# Bi_Dir_Circuit.net
KiCad netlist of a schematic drawn in Altium Designer
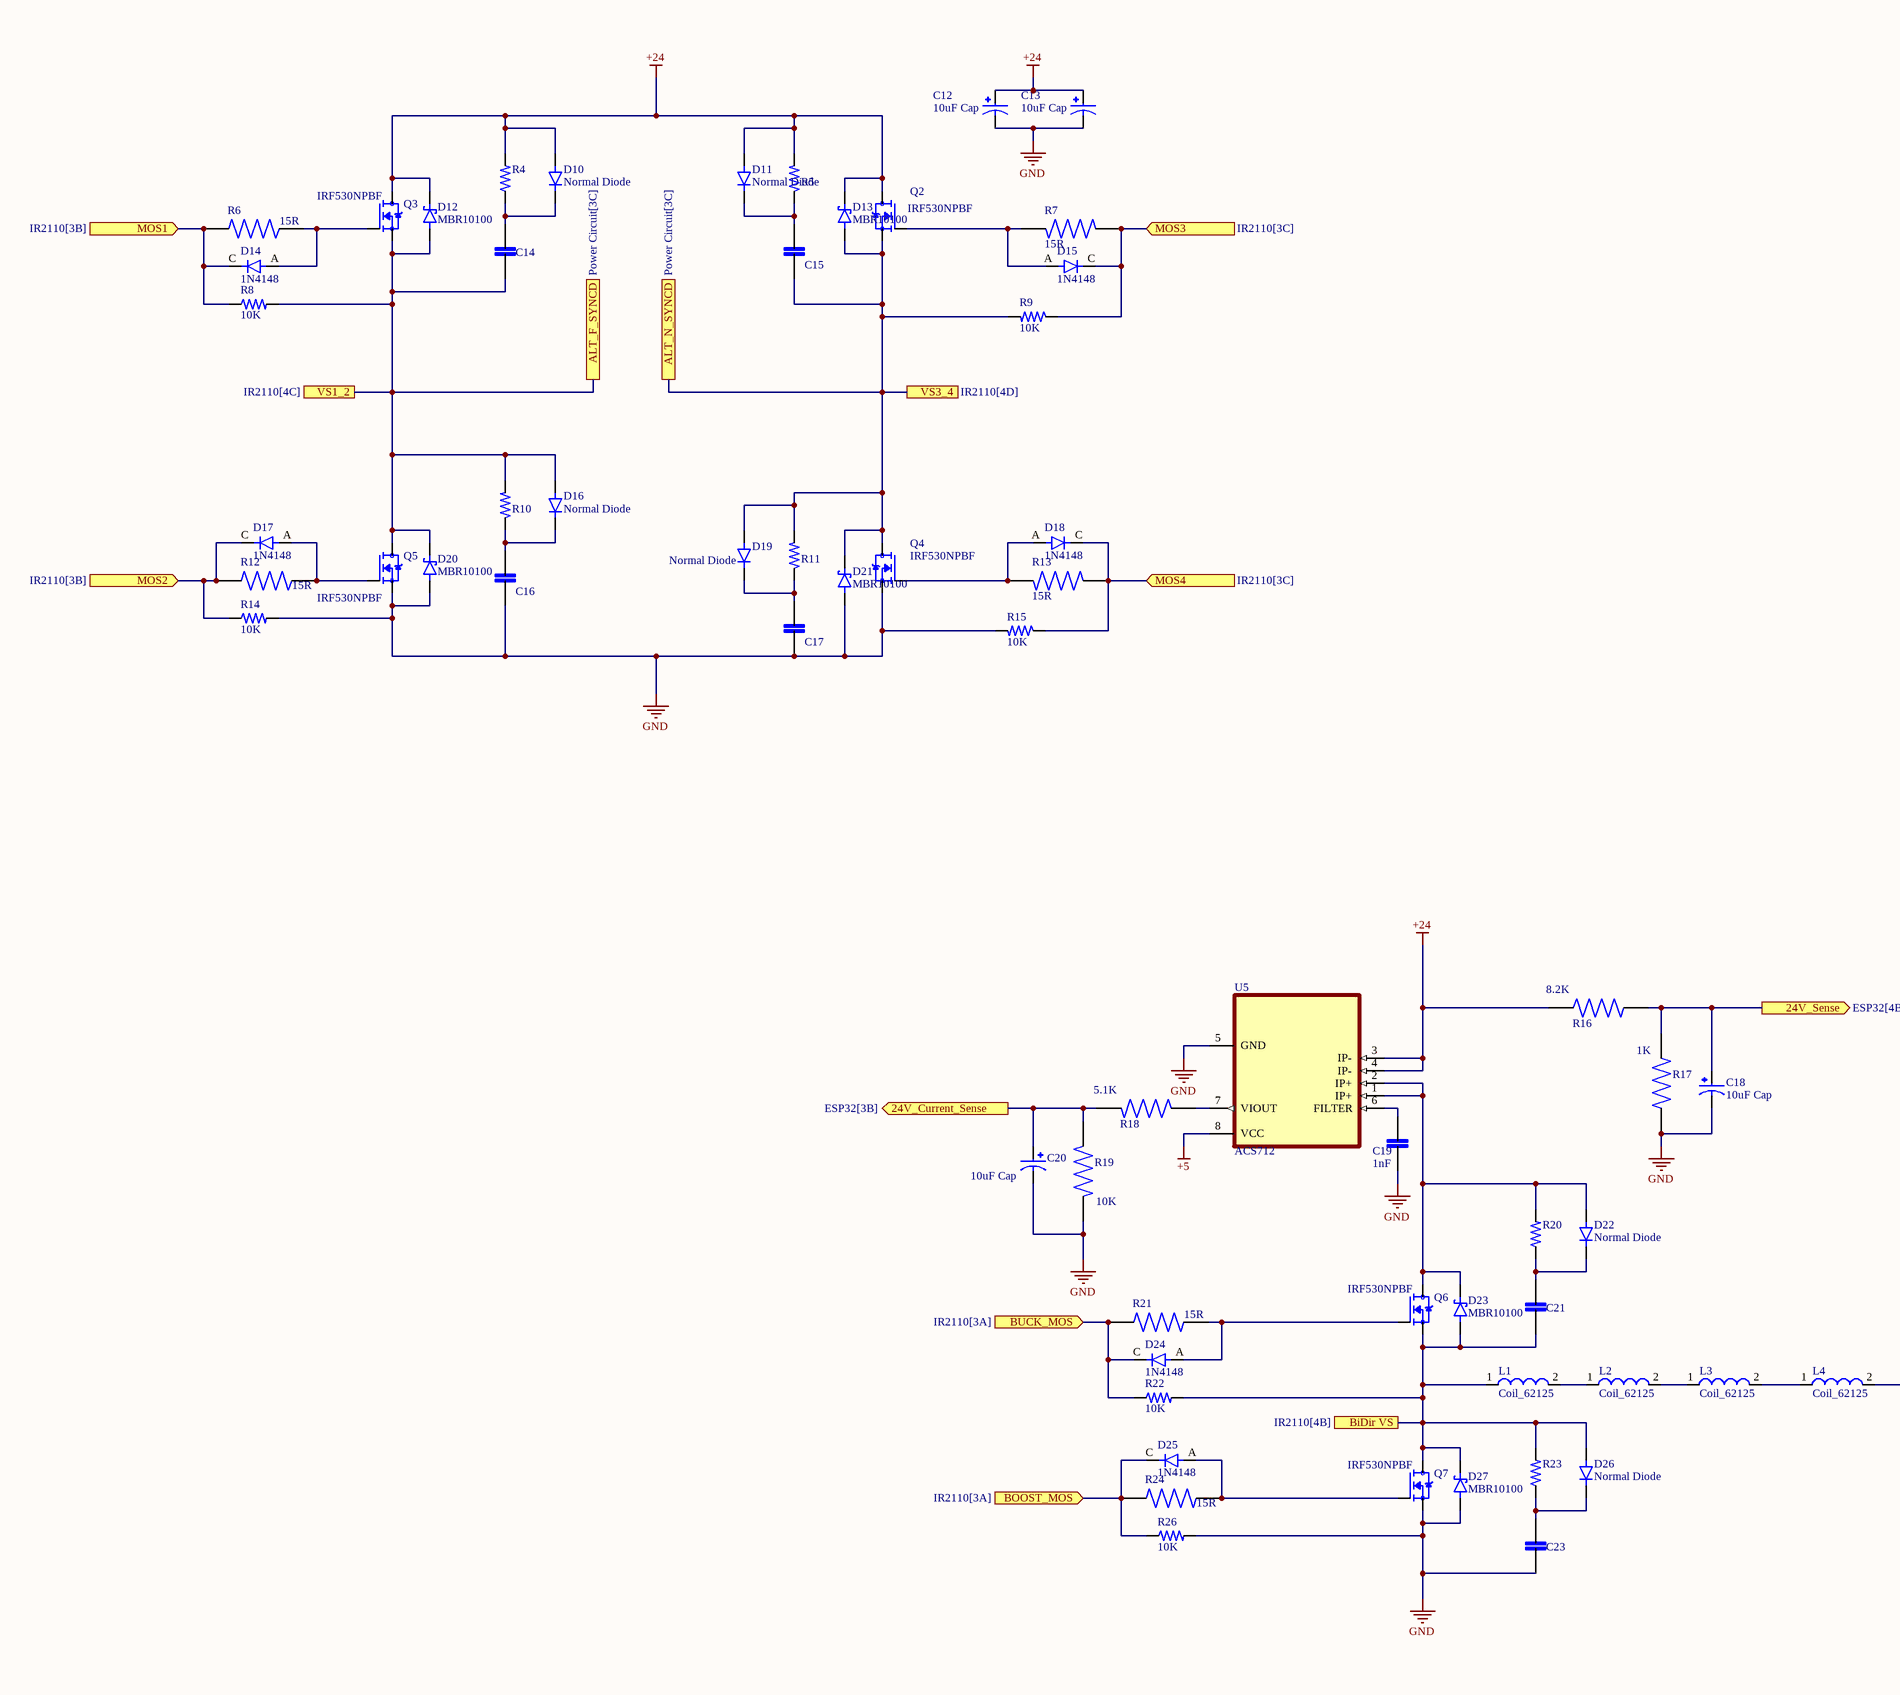
[diagram p0: Bi_Dir_Circuit.SchDoc, left]
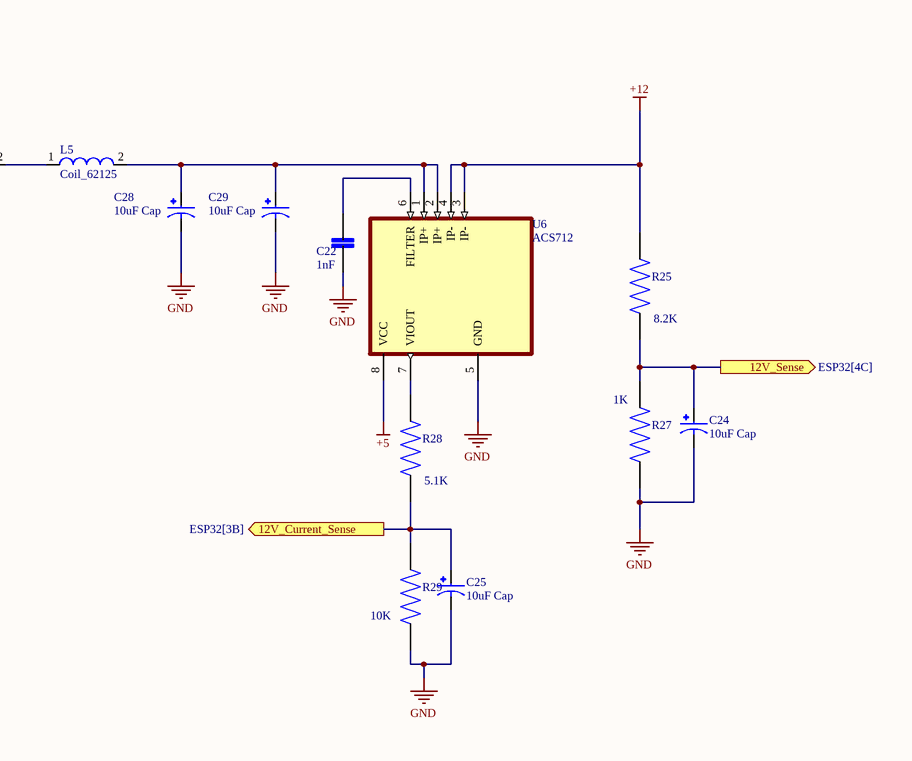
[diagram p1: Bi_Dir_Circuit.SchDoc, right]

(export (version "E")
  (design (tool "Eeschema 10.0.6"))
  (components
    (comp (ref "C12")
      (value "10uF Cap")
      (footprint "2200uF_Cap")
      (description "CAP ALUM 10UF 20% 50V RADIAL")
      (fields (field (name "MP") "ECE-A1HN100UI") (field (name "MF") "Panasonic"))
      (libsource (lib "MySCH_Library") (part "10uF Cap"))
    )
    (comp (ref "C13")
      (value "10uF Cap")
      (footprint "2200uF_Cap")
      (description "CAP ALUM 10UF 20% 50V RADIAL")
      (fields (field (name "MP") "ECE-A1HN100UI") (field (name "MF") "Panasonic"))
      (libsource (lib "MySCH_Library") (part "10uF Cap"))
    )
    (comp (ref "C14")
      (value "Ceramic Capacitor")
      (footprint "Ceramic Capacitor")
      (fields (field (name "MP") "LD051A121KAB2A") (field (name "MF") "AVX"))
      (libsource (lib "Capacitors Through Hole") (part "Ceramic Capacitor"))
    )
    (comp (ref "C15")
      (value "Ceramic Capacitor")
      (footprint "Ceramic Capacitor")
      (fields (field (name "MP") "LD051A121KAB2A") (field (name "MF") "AVX"))
      (libsource (lib "") (part "Ceramic Capacitor_1"))
    )
    (comp (ref "C16")
      (value "Ceramic Capacitor")
      (footprint "Ceramic Capacitor")
      (fields (field (name "MP") "LD051A121KAB2A") (field (name "MF") "AVX"))
      (libsource (lib "") (part "Ceramic Capacitor_1"))
    )
    (comp (ref "C17")
      (value "Ceramic Capacitor")
      (footprint "Ceramic Capacitor")
      (fields (field (name "MP") "LD051A121KAB2A") (field (name "MF") "AVX"))
      (libsource (lib "") (part "Ceramic Capacitor_1"))
    )
    (comp (ref "C18")
      (value "10uF Cap")
      (footprint "CAP_10uF")
      (description "CAP ALUM 10UF 20% 50V RADIAL")
      (fields (field (name "MP") "ECE-A1HN100UI") (field (name "MF") "Panasonic"))
      (libsource (lib "MySCH_Library") (part "10uF Cap"))
    )
    (comp (ref "C19")
      (value "1nF")
      (footprint "Ceramic Capacitor")
      (fields (field (name "MP") "LD051A121KAB2A") (field (name "MF") "AVX"))
      (libsource (lib "Capacitors Through Hole") (part "Ceramic Capacitor"))
    )
    (comp (ref "C20")
      (value "10uF Cap")
      (footprint "CAP_10uF")
      (description "CAP ALUM 10UF 20% 50V RADIAL")
      (fields (field (name "MP") "ECE-A1HN100UI") (field (name "MF") "Panasonic"))
      (libsource (lib "") (part "10uF Cap_1"))
    )
    (comp (ref "C21")
      (value "Ceramic Capacitor")
      (footprint "Ceramic Capacitor")
      (fields (field (name "MP") "LD051A121KAB2A") (field (name "MF") "AVX"))
      (libsource (lib "Capacitors Through Hole") (part "Ceramic Capacitor"))
    )
    (comp (ref "C22")
      (value "1nF")
      (footprint "Ceramic Capacitor")
      (fields (field (name "MP") "LD051A121KAB2A") (field (name "MF") "AVX"))
      (libsource (lib "Capacitors Through Hole") (part "Ceramic Capacitor"))
    )
    (comp (ref "C23")
      (value "Ceramic Capacitor")
      (footprint "Ceramic Capacitor")
      (fields (field (name "MP") "LD051A121KAB2A") (field (name "MF") "AVX"))
      (libsource (lib "Capacitors Through Hole") (part "Ceramic Capacitor"))
    )
    (comp (ref "C24")
      (value "10uF Cap")
      (footprint "CAP_10uF")
      (description "CAP ALUM 10UF 20% 50V RADIAL")
      (fields (field (name "MP") "ECE-A1HN100UI") (field (name "MF") "Panasonic"))
      (libsource (lib "MySCH_Library") (part "10uF Cap"))
    )
    (comp (ref "C25")
      (value "10uF Cap")
      (footprint "CAP_10uF")
      (description "CAP ALUM 10UF 20% 50V RADIAL")
      (fields (field (name "MP") "ECE-A1HN100UI") (field (name "MF") "Panasonic"))
      (libsource (lib "MySCH_Library") (part "10uF Cap"))
    )
    (comp (ref "C28")
      (value "10uF Cap")
      (footprint "2200uF_Cap")
      (description "CAP ALUM 10UF 20% 50V RADIAL")
      (fields (field (name "MP") "ECE-A1HN100UI") (field (name "MF") "Panasonic"))
      (libsource (lib "MySCH_Library") (part "10uF Cap"))
    )
    (comp (ref "C29")
      (value "10uF Cap")
      (footprint "2200uF_Cap")
      (description "CAP ALUM 10UF 20% 50V RADIAL")
      (fields (field (name "MP") "ECE-A1HN100UI") (field (name "MF") "Panasonic"))
      (libsource (lib "MySCH_Library") (part "10uF Cap"))
    )
    (comp (ref "D10")
      (value "Normal Diode")
      (footprint "Common Trhough Hole")
      (fields (field (name "MF") "NTE Electronics, Inc.") (field (name "MP") "1N4007"))
      (libsource (lib "Diodes Through Hole") (part "Normal Diode"))
    )
    (comp (ref "D11")
      (value "Normal Diode")
      (footprint "Common Trhough Hole")
      (fields (field (name "MF") "NTE Electronics, Inc.") (field (name "MP") "1N4007"))
      (libsource (lib "Diodes Through Hole") (part "Normal Diode"))
    )
    (comp (ref "D12")
      (value "MBR10100")
      (footprint "MBR10100")
      (fields (field (name "MF") "Diodes Inc.") (field (name "MP") "1N5817-T"))
      (libsource (lib "Diodes Through Hole") (part "MBR10100"))
    )
    (comp (ref "D13")
      (value "MBR10100")
      (footprint "MBR10100")
      (fields (field (name "MF") "Diodes Inc.") (field (name "MP") "1N5817-T"))
      (libsource (lib "Diodes Through Hole") (part "MBR10100"))
    )
    (comp (ref "D14")
      (value "1N4148")
      (footprint "1N4007 DIODE")
      (description "Diode Standard 1000 V 1A Through Hole DO-41")
      (fields (field (name "MF") "NTE Electronics, Inc.") (field (name "MP") "1N4007"))
      (libsource (lib "MySCH_Library") (part "1N4007"))
    )
    (comp (ref "D15")
      (value "1N4148")
      (footprint "1N4007 DIODE")
      (description "Diode Standard 1000 V 1A Through Hole DO-41")
      (fields (field (name "MF") "NTE Electronics, Inc.") (field (name "MP") "1N4007"))
      (libsource (lib "MySCH_Library") (part "1N4007"))
    )
    (comp (ref "D16")
      (value "Normal Diode")
      (footprint "Common Trhough Hole")
      (fields (field (name "MF") "NTE Electronics, Inc.") (field (name "MP") "1N4007"))
      (libsource (lib "Diodes Through Hole") (part "Normal Diode"))
    )
    (comp (ref "D17")
      (value "1N4148")
      (footprint "1N4007 DIODE")
      (description "Diode Standard 1000 V 1A Through Hole DO-41")
      (fields (field (name "MF") "NTE Electronics, Inc.") (field (name "MP") "1N4007"))
      (libsource (lib "MySCH_Library") (part "1N4007"))
    )
    (comp (ref "D18")
      (value "1N4148")
      (footprint "1N4007 DIODE")
      (description "Diode Standard 1000 V 1A Through Hole DO-41")
      (fields (field (name "MF") "NTE Electronics, Inc.") (field (name "MP") "1N4007"))
      (libsource (lib "MySCH_Library") (part "1N4007"))
    )
    (comp (ref "D19")
      (value "Normal Diode")
      (footprint "Common Trhough Hole")
      (fields (field (name "MF") "NTE Electronics, Inc.") (field (name "MP") "1N4007"))
      (libsource (lib "Diodes Through Hole") (part "Normal Diode"))
    )
    (comp (ref "D20")
      (value "MBR10100")
      (footprint "MBR10100")
      (fields (field (name "MF") "Diodes Inc.") (field (name "MP") "1N5817-T"))
      (libsource (lib "Diodes Through Hole") (part "MBR10100"))
    )
    (comp (ref "D21")
      (value "MBR10100")
      (footprint "MBR10100")
      (fields (field (name "MF") "Diodes Inc.") (field (name "MP") "1N5817-T"))
      (libsource (lib "Diodes Through Hole") (part "MBR10100"))
    )
    (comp (ref "D22")
      (value "Normal Diode")
      (footprint "Common Trhough Hole")
      (fields (field (name "MF") "NTE Electronics, Inc.") (field (name "MP") "1N4007"))
      (libsource (lib "Diodes Through Hole") (part "Normal Diode"))
    )
    (comp (ref "D23")
      (value "MBR10100")
      (footprint "MBR10100")
      (fields (field (name "MF") "Diodes Inc.") (field (name "MP") "1N5817-T"))
      (libsource (lib "Diodes Through Hole") (part "MBR10100"))
    )
    (comp (ref "D24")
      (value "1N4148")
      (footprint "1N4007 DIODE")
      (description "Diode Standard 1000 V 1A Through Hole DO-41")
      (fields (field (name "MF") "NTE Electronics, Inc.") (field (name "MP") "1N4007"))
      (libsource (lib "MySCH_Library") (part "1N4007"))
    )
    (comp (ref "D25")
      (value "1N4148")
      (footprint "1N4007 DIODE")
      (description "Diode Standard 1000 V 1A Through Hole DO-41")
      (fields (field (name "MF") "NTE Electronics, Inc.") (field (name "MP") "1N4007"))
      (libsource (lib "MySCH_Library") (part "1N4007"))
    )
    (comp (ref "D26")
      (value "Normal Diode")
      (footprint "Common Trhough Hole")
      (fields (field (name "MF") "NTE Electronics, Inc.") (field (name "MP") "1N4007"))
      (libsource (lib "Diodes Through Hole") (part "Normal Diode"))
    )
    (comp (ref "D27")
      (value "MBR10100")
      (footprint "MBR10100")
      (fields (field (name "MF") "Diodes Inc.") (field (name "MP") "1N5817-T"))
      (libsource (lib "Diodes Through Hole") (part "MBR10100"))
    )
    (comp (ref "L1")
      (value "Coil_62125")
      (footprint "Coil 65125")
      (description "Inductor Power Wirewound 470uH 10% 1KHz 25Q-Factor Ferrite 210mA 3.3Ohm DCR T/R")
      (fields (field (name "DIGI-KEY_PART_NUMBER") "SDR0604-471KLCT-ND") (field (name "MF") "Bourns"))
      (libsource (lib "MySCH_Library") (part "Coil_62125"))
    )
    (comp (ref "L2")
      (value "Coil_62125")
      (footprint "Coil 65125")
      (description "Inductor Power Wirewound 470uH 10% 1KHz 25Q-Factor Ferrite 210mA 3.3Ohm DCR T/R")
      (fields (field (name "DIGI-KEY_PART_NUMBER") "SDR0604-471KLCT-ND") (field (name "MF") "Bourns"))
      (libsource (lib "MySCH_Library") (part "Coil_62125"))
    )
    (comp (ref "L3")
      (value "Coil_62125")
      (footprint "Coil 65125")
      (description "Inductor Power Wirewound 470uH 10% 1KHz 25Q-Factor Ferrite 210mA 3.3Ohm DCR T/R")
      (fields (field (name "DIGI-KEY_PART_NUMBER") "SDR0604-471KLCT-ND") (field (name "MF") "Bourns"))
      (libsource (lib "MySCH_Library") (part "Coil_62125"))
    )
    (comp (ref "L4")
      (value "Coil_62125")
      (footprint "Coil 65125")
      (description "Inductor Power Wirewound 470uH 10% 1KHz 25Q-Factor Ferrite 210mA 3.3Ohm DCR T/R")
      (fields (field (name "DIGI-KEY_PART_NUMBER") "SDR0604-471KLCT-ND") (field (name "MF") "Bourns"))
      (libsource (lib "MySCH_Library") (part "Coil_62125"))
    )
    (comp (ref "L5")
      (value "Coil_62125")
      (footprint "Coil 65125")
      (description "Inductor Power Wirewound 470uH 10% 1KHz 25Q-Factor Ferrite 210mA 3.3Ohm DCR T/R")
      (fields (field (name "DIGI-KEY_PART_NUMBER") "SDR0604-471KLCT-ND") (field (name "MF") "Bourns"))
      (libsource (lib "MySCH_Library") (part "Coil_62125"))
    )
    (comp (ref "Q2")
      (value "IRF530NPBF")
      (footprint "IRF530N")
      (fields (field (name "MF") "Infineon Technologies"))
      (libsource (lib "MySCH_Library") (part "IRF530NPBF"))
    )
    (comp (ref "Q3")
      (value "IRF530NPBF")
      (footprint "IRF530N")
      (fields (field (name "MF") "Infineon Technologies"))
      (libsource (lib "MySCH_Library") (part "IRF530NPBF"))
    )
    (comp (ref "Q4")
      (value "IRF530NPBF")
      (footprint "IRF530N")
      (fields (field (name "MF") "Infineon Technologies"))
      (libsource (lib "MySCH_Library") (part "IRF530NPBF"))
    )
    (comp (ref "Q5")
      (value "IRF530NPBF")
      (footprint "IRF530N")
      (fields (field (name "MF") "Infineon Technologies"))
      (libsource (lib "MySCH_Library") (part "IRF530NPBF"))
    )
    (comp (ref "Q6")
      (value "IRF530NPBF")
      (footprint "IRF530N")
      (fields (field (name "MF") "Infineon Technologies"))
      (libsource (lib "MySCH_Library") (part "IRF530NPBF"))
    )
    (comp (ref "Q7")
      (value "IRF530NPBF")
      (footprint "IRF530N")
      (fields (field (name "MF") "Infineon Technologies"))
      (libsource (lib "MySCH_Library") (part "IRF530NPBF"))
    )
    (comp (ref "R4")
      (value "Resistor")
      (footprint "Resistor_Through Hole")
      (fields
        (field (name "MP") "2-2176053-0")
        (field (name "TOLERANCE") "1%")
        (field (name "MF") "TE Connectivity")
      )
      (libsource (lib "Resistors Through Hole") (part "Resistor"))
    )
    (comp (ref "R5")
      (value "Resistor")
      (footprint "Resistor_Through Hole")
      (fields
        (field (name "MP") "2-2176053-0")
        (field (name "TOLERANCE") "1%")
        (field (name "MF") "TE Connectivity")
      )
      (libsource (lib "Resistors Through Hole") (part "Resistor"))
    )
    (comp (ref "R6")
      (value "15R")
      (footprint "Resistor_Through Hole")
      (description "1.02 Ohms Â±1% 0.25W, 1/4W Through Hole Resistor Axial Metal Film")
      (fields (field (name "MP") "MFR-25FTE52-1R") (field (name "MF") "Yageo"))
      (libsource (lib "MySCH_Library") (part "Resistor_Through Hole"))
    )
    (comp (ref "R7")
      (value "15R")
      (footprint "Resistor_Through Hole")
      (description "1.02 Ohms Â±1% 0.25W, 1/4W Through Hole Resistor Axial Metal Film")
      (fields (field (name "MP") "MFR-25FTE52-1R") (field (name "MF") "Yageo"))
      (libsource (lib "MySCH_Library") (part "Resistor_Through Hole"))
    )
    (comp (ref "R8")
      (value "10K")
      (footprint "Resistor_Through Hole")
      (fields
        (field (name "MP") "2-2176053-0")
        (field (name "TOLERANCE") "1%")
        (field (name "MF") "TE Connectivity")
      )
      (libsource (lib "Resistors Through Hole") (part "Resistor"))
    )
    (comp (ref "R9")
      (value "10K")
      (footprint "Resistor_Through Hole")
      (fields
        (field (name "MP") "2-2176053-0")
        (field (name "TOLERANCE") "1%")
        (field (name "MF") "TE Connectivity")
      )
      (libsource (lib "Resistors Through Hole") (part "Resistor"))
    )
    (comp (ref "R10")
      (value "Resistor")
      (footprint "Resistor_Through Hole")
      (fields
        (field (name "MP") "2-2176053-0")
        (field (name "TOLERANCE") "1%")
        (field (name "MF") "TE Connectivity")
      )
      (libsource (lib "Resistors Through Hole") (part "Resistor"))
    )
    (comp (ref "R11")
      (value "Resistor")
      (footprint "Resistor_Through Hole")
      (fields
        (field (name "MP") "2-2176053-0")
        (field (name "TOLERANCE") "1%")
        (field (name "MF") "TE Connectivity")
      )
      (libsource (lib "Resistors Through Hole") (part "Resistor"))
    )
    (comp (ref "R12")
      (value "15R")
      (footprint "Resistor_Through Hole")
      (description "1.02 Ohms Â±1% 0.25W, 1/4W Through Hole Resistor Axial Metal Film")
      (fields (field (name "MP") "MFR-25FTE52-1R") (field (name "MF") "Yageo"))
      (libsource (lib "MySCH_Library") (part "Resistor_Through Hole"))
    )
    (comp (ref "R13")
      (value "15R")
      (footprint "Resistor_Through Hole")
      (description "1.02 Ohms Â±1% 0.25W, 1/4W Through Hole Resistor Axial Metal Film")
      (fields (field (name "MP") "MFR-25FTE52-1R") (field (name "MF") "Yageo"))
      (libsource (lib "MySCH_Library") (part "Resistor_Through Hole"))
    )
    (comp (ref "R14")
      (value "10K")
      (footprint "Resistor_Through Hole")
      (fields
        (field (name "MP") "2-2176053-0")
        (field (name "TOLERANCE") "1%")
        (field (name "MF") "TE Connectivity")
      )
      (libsource (lib "Resistors Through Hole") (part "Resistor"))
    )
    (comp (ref "R15")
      (value "10K")
      (footprint "Resistor_Through Hole")
      (fields
        (field (name "MP") "2-2176053-0")
        (field (name "TOLERANCE") "1%")
        (field (name "MF") "TE Connectivity")
      )
      (libsource (lib "Resistors Through Hole") (part "Resistor"))
    )
    (comp (ref "R16")
      (value "8.2K")
      (footprint "Resistor_Through Hole")
      (description "1.02 Ohms Â±1% 0.25W, 1/4W Through Hole Resistor Axial Metal Film")
      (fields (field (name "MP") "MFR-25FTE52-1R") (field (name "MF") "Yageo"))
      (libsource (lib "MySCH_Library") (part "Resistor_Through Hole"))
    )
    (comp (ref "R17")
      (value "1K")
      (footprint "Resistor_Through Hole")
      (description "1.02 Ohms Â±1% 0.25W, 1/4W Through Hole Resistor Axial Metal Film")
      (fields (field (name "MP") "MFR-25FTE52-1R") (field (name "MF") "Yageo"))
      (libsource (lib "MySCH_Library") (part "Resistor_Through Hole"))
    )
    (comp (ref "R18")
      (value "5.1K")
      (footprint "Resistor_Through Hole")
      (description "1.02 Ohms Â±1% 0.25W, 1/4W Through Hole Resistor Axial Metal Film")
      (fields (field (name "MP") "MFR-25FTE52-1R") (field (name "MF") "Yageo"))
      (libsource (lib "MySCH_Library") (part "Resistor_Through Hole"))
    )
    (comp (ref "R19")
      (value "10K")
      (footprint "Resistor_Through Hole")
      (description "1.02 Ohms Â±1% 0.25W, 1/4W Through Hole Resistor Axial Metal Film")
      (fields (field (name "MP") "MFR-25FTE52-1R") (field (name "MF") "Yageo"))
      (libsource (lib "MySCH_Library") (part "Resistor_Through Hole"))
    )
    (comp (ref "R20")
      (value "Resistor")
      (footprint "Resistor_Through Hole")
      (fields
        (field (name "MP") "2-2176053-0")
        (field (name "TOLERANCE") "1%")
        (field (name "MF") "TE Connectivity")
      )
      (libsource (lib "Resistors Through Hole") (part "Resistor"))
    )
    (comp (ref "R21")
      (value "15R")
      (footprint "Resistor_Through Hole")
      (description "1.02 Ohms Â±1% 0.25W, 1/4W Through Hole Resistor Axial Metal Film")
      (fields (field (name "MP") "MFR-25FTE52-1R") (field (name "MF") "Yageo"))
      (libsource (lib "MySCH_Library") (part "Resistor_Through Hole"))
    )
    (comp (ref "R22")
      (value "10K")
      (footprint "Resistor_Through Hole")
      (fields
        (field (name "MP") "2-2176053-0")
        (field (name "TOLERANCE") "1%")
        (field (name "MF") "TE Connectivity")
      )
      (libsource (lib "Resistors Through Hole") (part "Resistor"))
    )
    (comp (ref "R23")
      (value "Resistor")
      (footprint "Resistor_Through Hole")
      (fields
        (field (name "MP") "2-2176053-0")
        (field (name "TOLERANCE") "1%")
        (field (name "MF") "TE Connectivity")
      )
      (libsource (lib "Resistors Through Hole") (part "Resistor"))
    )
    (comp (ref "R24")
      (value "15R")
      (footprint "Resistor_Through Hole")
      (description "1.02 Ohms Â±1% 0.25W, 1/4W Through Hole Resistor Axial Metal Film")
      (fields (field (name "MP") "MFR-25FTE52-1R") (field (name "MF") "Yageo"))
      (libsource (lib "MySCH_Library") (part "Resistor_Through Hole"))
    )
    (comp (ref "R25")
      (value "8.2K")
      (footprint "Resistor_Through Hole")
      (description "1.02 Ohms Â±1% 0.25W, 1/4W Through Hole Resistor Axial Metal Film")
      (fields (field (name "MP") "MFR-25FTE52-1R") (field (name "MF") "Yageo"))
      (libsource (lib "MySCH_Library") (part "Resistor_Through Hole"))
    )
    (comp (ref "R26")
      (value "10K")
      (footprint "Resistor_Through Hole")
      (fields
        (field (name "MP") "2-2176053-0")
        (field (name "TOLERANCE") "1%")
        (field (name "MF") "TE Connectivity")
      )
      (libsource (lib "Resistors Through Hole") (part "Resistor"))
    )
    (comp (ref "R27")
      (value "1K")
      (footprint "Resistor_Through Hole")
      (description "1.02 Ohms Â±1% 0.25W, 1/4W Through Hole Resistor Axial Metal Film")
      (fields (field (name "MP") "MFR-25FTE52-1R") (field (name "MF") "Yageo"))
      (libsource (lib "MySCH_Library") (part "Resistor_Through Hole"))
    )
    (comp (ref "R28")
      (value "5.1K")
      (footprint "Resistor_Through Hole")
      (description "1.02 Ohms Â±1% 0.25W, 1/4W Through Hole Resistor Axial Metal Film")
      (fields (field (name "MP") "MFR-25FTE52-1R") (field (name "MF") "Yageo"))
      (libsource (lib "MySCH_Library") (part "Resistor_Through Hole"))
    )
    (comp (ref "R29")
      (value "10K")
      (footprint "Resistor_Through Hole")
      (description "1.02 Ohms Â±1% 0.25W, 1/4W Through Hole Resistor Axial Metal Film")
      (fields (field (name "MP") "MFR-25FTE52-1R") (field (name "MF") "Yageo"))
      (libsource (lib "MySCH_Library") (part "Resistor_Through Hole"))
    )
    (comp (ref "U5")
      (value "ACS712")
      (footprint "ACS712")
      (description "Current Sensor 5A 1 Channel Hall Effect, Open Loop Bidirectional 8-SOIC (0.154, 3.90mm Width)")
      (fields (field (name "MP") "ACS712ELCTR-05B-T") (field (name "MF") "Allegro MicroSystems LLC"))
      (libsource (lib "Hall Current Sensor") (part "ACS712"))
    )
    (comp (ref "U6")
      (value "ACS712")
      (footprint "ACS712")
      (description "Current Sensor 5A 1 Channel Hall Effect, Open Loop Bidirectional 8-SOIC (0.154, 3.90mm Width)")
      (fields (field (name "MP") "ACS712ELCTR-05B-T") (field (name "MF") "Allegro MicroSystems LLC"))
      (libsource (lib "Hall Current Sensor") (part "ACS712"))
    )
  )
  (nets
    (net (code "1") (name "+5") (class "Default")
      (node (ref "U5") (pin "8") (pinfunction "VCC_8") (pintype "power_in"))
      (node (ref "U6") (pin "8") (pinfunction "VCC_8") (pintype "power_in"))
    )
    (net (code "2") (name "+12") (class "Default")
      (node (ref "R25") (pin "2") (pinfunction "2_2") (pintype "passive"))
      (node (ref "U6") (pin "3") (pinfunction "IP-_3") (pintype "input"))
      (node (ref "U6") (pin "4") (pinfunction "IP-_4") (pintype "input"))
    )
    (net (code "3") (name "+24") (class "Default")
      (node (ref "C12") (pin "P") (pinfunction "P_P") (pintype "passive"))
      (node (ref "C13") (pin "P") (pinfunction "P_P") (pintype "passive"))
      (node (ref "D10") (pin "2") (pinfunction "A_2") (pintype "passive"))
      (node (ref "D11") (pin "2") (pinfunction "A_2") (pintype "passive"))
      (node (ref "D12") (pin "1") (pinfunction "K_1") (pintype "passive"))
      (node (ref "D13") (pin "1") (pinfunction "K_1") (pintype "passive"))
      (node (ref "Q2") (pin "2") (pinfunction "D_2") (pintype "passive"))
      (node (ref "Q3") (pin "2") (pinfunction "D_2") (pintype "passive"))
      (node (ref "R16") (pin "1") (pinfunction "1_1") (pintype "passive"))
      (node (ref "R4") (pin "2") (pinfunction "2_2") (pintype "passive"))
      (node (ref "R5") (pin "2") (pinfunction "2_2") (pintype "passive"))
      (node (ref "U5") (pin "3") (pinfunction "IP-_3") (pintype "input"))
      (node (ref "U5") (pin "4") (pinfunction "IP-_4") (pintype "input"))
    )
    (net (code "4") (name "/12V_Current_Sense") (class "Default")
      (node (ref "C25") (pin "P") (pinfunction "P_P") (pintype "passive"))
      (node (ref "R28") (pin "1") (pinfunction "1_1") (pintype "passive"))
      (node (ref "R29") (pin "2") (pinfunction "2_2") (pintype "passive"))
    )
    (net (code "5") (name "/12V_Sense") (class "Default")
      (node (ref "C24") (pin "P") (pinfunction "P_P") (pintype "passive"))
      (node (ref "R25") (pin "1") (pinfunction "1_1") (pintype "passive"))
      (node (ref "R27") (pin "2") (pinfunction "2_2") (pintype "passive"))
    )
    (net (code "6") (name "/24V_Current_Sense") (class "Default")
      (node (ref "C20") (pin "P") (pinfunction "P_P") (pintype "passive"))
      (node (ref "R18") (pin "1") (pinfunction "1_1") (pintype "passive"))
      (node (ref "R19") (pin "2") (pinfunction "2_2") (pintype "passive"))
    )
    (net (code "7") (name "/24V_Sense") (class "Default")
      (node (ref "C18") (pin "P") (pinfunction "P_P") (pintype "passive"))
      (node (ref "R16") (pin "2") (pinfunction "2_2") (pintype "passive"))
      (node (ref "R17") (pin "2") (pinfunction "2_2") (pintype "passive"))
    )
    (net (code "8") (name "/ALT_F_SYNCD") (class "Default")
      (node (ref "C14") (pin "1") (pinfunction "1_1") (pintype "passive"))
      (node (ref "D12") (pin "3") (pinfunction "A_3") (pintype "passive"))
      (node (ref "D16") (pin "2") (pinfunction "A_2") (pintype "passive"))
      (node (ref "D20") (pin "1") (pinfunction "K_1") (pintype "passive"))
      (node (ref "Q3") (pin "3") (pinfunction "S_3") (pintype "passive"))
      (node (ref "Q5") (pin "2") (pinfunction "D_2") (pintype "passive"))
      (node (ref "R10") (pin "2") (pinfunction "2_2") (pintype "passive"))
      (node (ref "R8") (pin "2") (pinfunction "2_2") (pintype "passive"))
    )
    (net (code "9") (name "/ALT_N_SYNCD") (class "Default")
      (node (ref "C15") (pin "1") (pinfunction "1_1") (pintype "passive"))
      (node (ref "D13") (pin "3") (pinfunction "A_3") (pintype "passive"))
      (node (ref "D19") (pin "2") (pinfunction "A_2") (pintype "passive"))
      (node (ref "D21") (pin "1") (pinfunction "K_1") (pintype "passive"))
      (node (ref "Q2") (pin "3") (pinfunction "S_3") (pintype "passive"))
      (node (ref "Q4") (pin "2") (pinfunction "D_2") (pintype "passive"))
      (node (ref "R11") (pin "2") (pinfunction "2_2") (pintype "passive"))
      (node (ref "R9") (pin "2") (pinfunction "2_2") (pintype "passive"))
    )
    (net (code "10") (name "/BOOST_MOS") (class "Default")
      (node (ref "D25") (pin "C") (pinfunction "C_C") (pintype "passive"))
      (node (ref "R24") (pin "1") (pinfunction "1_1") (pintype "passive"))
      (node (ref "R26") (pin "1") (pinfunction "1_1") (pintype "passive"))
    )
    (net (code "11") (name "/BUCK_MOS") (class "Default")
      (node (ref "D24") (pin "C") (pinfunction "C_C") (pintype "passive"))
      (node (ref "R21") (pin "1") (pinfunction "1_1") (pintype "passive"))
      (node (ref "R22") (pin "1") (pinfunction "1_1") (pintype "passive"))
    )
    (net (code "12") (name "/BiDir VS") (class "Default")
      (node (ref "C21") (pin "1") (pinfunction "1_1") (pintype "passive"))
      (node (ref "D23") (pin "3") (pinfunction "A_3") (pintype "passive"))
      (node (ref "D26") (pin "2") (pinfunction "A_2") (pintype "passive"))
      (node (ref "D27") (pin "1") (pinfunction "K_1") (pintype "passive"))
      (node (ref "L1") (pin "1") (pinfunction "1_1") (pintype "passive"))
      (node (ref "Q6") (pin "3") (pinfunction "S_3") (pintype "passive"))
      (node (ref "Q7") (pin "2") (pinfunction "D_2") (pintype "passive"))
      (node (ref "R22") (pin "2") (pinfunction "2_2") (pintype "passive"))
      (node (ref "R23") (pin "2") (pinfunction "2_2") (pintype "passive"))
    )
    (net (code "13") (name "/MOS1") (class "Default")
      (node (ref "D14") (pin "C") (pinfunction "C_C") (pintype "passive"))
      (node (ref "R6") (pin "1") (pinfunction "1_1") (pintype "passive"))
      (node (ref "R8") (pin "1") (pinfunction "1_1") (pintype "passive"))
    )
    (net (code "14") (name "/MOS2") (class "Default")
      (node (ref "D17") (pin "C") (pinfunction "C_C") (pintype "passive"))
      (node (ref "R12") (pin "1") (pinfunction "1_1") (pintype "passive"))
      (node (ref "R14") (pin "1") (pinfunction "1_1") (pintype "passive"))
    )
    (net (code "15") (name "/MOS3") (class "Default")
      (node (ref "D15") (pin "C") (pinfunction "C_C") (pintype "passive"))
      (node (ref "R7") (pin "1") (pinfunction "1_1") (pintype "passive"))
      (node (ref "R9") (pin "1") (pinfunction "1_1") (pintype "passive"))
    )
    (net (code "16") (name "/MOS4") (class "Default")
      (node (ref "D18") (pin "C") (pinfunction "C_C") (pintype "passive"))
      (node (ref "R13") (pin "1") (pinfunction "1_1") (pintype "passive"))
      (node (ref "R15") (pin "1") (pinfunction "1_1") (pintype "passive"))
    )
    (net (code "17") (name "GND") (class "Default")
      (node (ref "C12") (pin "N") (pinfunction "N_N") (pintype "passive"))
      (node (ref "C13") (pin "N") (pinfunction "N_N") (pintype "passive"))
      (node (ref "C16") (pin "1") (pinfunction "1_1") (pintype "passive"))
      (node (ref "C17") (pin "1") (pinfunction "1_1") (pintype "passive"))
      (node (ref "C18") (pin "N") (pinfunction "N_N") (pintype "passive"))
      (node (ref "C19") (pin "1") (pinfunction "1_1") (pintype "passive"))
      (node (ref "C20") (pin "N") (pinfunction "N_N") (pintype "passive"))
      (node (ref "C22") (pin "1") (pinfunction "1_1") (pintype "passive"))
      (node (ref "C23") (pin "1") (pinfunction "1_1") (pintype "passive"))
      (node (ref "C24") (pin "N") (pinfunction "N_N") (pintype "passive"))
      (node (ref "C25") (pin "N") (pinfunction "N_N") (pintype "passive"))
      (node (ref "C28") (pin "N") (pinfunction "N_N") (pintype "passive"))
      (node (ref "C29") (pin "N") (pinfunction "N_N") (pintype "passive"))
      (node (ref "D20") (pin "3") (pinfunction "A_3") (pintype "passive"))
      (node (ref "D21") (pin "3") (pinfunction "A_3") (pintype "passive"))
      (node (ref "D27") (pin "3") (pinfunction "A_3") (pintype "passive"))
      (node (ref "Q4") (pin "3") (pinfunction "S_3") (pintype "passive"))
      (node (ref "Q5") (pin "3") (pinfunction "S_3") (pintype "passive"))
      (node (ref "Q7") (pin "3") (pinfunction "S_3") (pintype "passive"))
      (node (ref "R14") (pin "2") (pinfunction "2_2") (pintype "passive"))
      (node (ref "R15") (pin "2") (pinfunction "2_2") (pintype "passive"))
      (node (ref "R17") (pin "1") (pinfunction "1_1") (pintype "passive"))
      (node (ref "R19") (pin "1") (pinfunction "1_1") (pintype "passive"))
      (node (ref "R26") (pin "2") (pinfunction "2_2") (pintype "passive"))
      (node (ref "R27") (pin "1") (pinfunction "1_1") (pintype "passive"))
      (node (ref "R29") (pin "1") (pinfunction "1_1") (pintype "passive"))
      (node (ref "U5") (pin "5") (pinfunction "GND_5") (pintype "power_in"))
      (node (ref "U6") (pin "5") (pinfunction "GND_5") (pintype "power_in"))
    )
    (net (code "18") (name "Net-(C28-PadP)") (class "Default")
      (node (ref "C28") (pin "P") (pinfunction "P_P") (pintype "passive"))
      (node (ref "C29") (pin "P") (pinfunction "P_P") (pintype "passive"))
      (node (ref "L5") (pin "2") (pinfunction "2_2") (pintype "passive"))
      (node (ref "U6") (pin "1") (pinfunction "IP+_1") (pintype "input"))
      (node (ref "U6") (pin "2") (pinfunction "IP+_2") (pintype "input"))
    )
    (net (code "19") (name "Net-(D10-K)") (class "Default")
      (node (ref "C14") (pin "2") (pinfunction "2_2") (pintype "passive"))
      (node (ref "D10") (pin "1") (pinfunction "K_1") (pintype "passive"))
      (node (ref "R4") (pin "1") (pinfunction "1_1") (pintype "passive"))
    )
    (net (code "20") (name "Net-(D11-K)") (class "Default")
      (node (ref "C15") (pin "2") (pinfunction "2_2") (pintype "passive"))
      (node (ref "D11") (pin "1") (pinfunction "K_1") (pintype "passive"))
      (node (ref "R5") (pin "1") (pinfunction "1_1") (pintype "passive"))
    )
    (net (code "21") (name "Net-(D16-K)") (class "Default")
      (node (ref "C16") (pin "2") (pinfunction "2_2") (pintype "passive"))
      (node (ref "D16") (pin "1") (pinfunction "K_1") (pintype "passive"))
      (node (ref "R10") (pin "1") (pinfunction "1_1") (pintype "passive"))
    )
    (net (code "22") (name "Net-(D19-K)") (class "Default")
      (node (ref "C17") (pin "2") (pinfunction "2_2") (pintype "passive"))
      (node (ref "D19") (pin "1") (pinfunction "K_1") (pintype "passive"))
      (node (ref "R11") (pin "1") (pinfunction "1_1") (pintype "passive"))
    )
    (net (code "23") (name "Net-(D22-A)") (class "Default")
      (node (ref "D22") (pin "2") (pinfunction "A_2") (pintype "passive"))
      (node (ref "D23") (pin "1") (pinfunction "K_1") (pintype "passive"))
      (node (ref "Q6") (pin "2") (pinfunction "D_2") (pintype "passive"))
      (node (ref "R20") (pin "2") (pinfunction "2_2") (pintype "passive"))
      (node (ref "U5") (pin "1") (pinfunction "IP+_1") (pintype "input"))
      (node (ref "U5") (pin "2") (pinfunction "IP+_2") (pintype "input"))
    )
    (net (code "24") (name "Net-(D22-K)") (class "Default")
      (node (ref "C21") (pin "2") (pinfunction "2_2") (pintype "passive"))
      (node (ref "D22") (pin "1") (pinfunction "K_1") (pintype "passive"))
      (node (ref "R20") (pin "1") (pinfunction "1_1") (pintype "passive"))
    )
    (net (code "25") (name "Net-(D26-K)") (class "Default")
      (node (ref "C23") (pin "2") (pinfunction "2_2") (pintype "passive"))
      (node (ref "D26") (pin "1") (pinfunction "K_1") (pintype "passive"))
      (node (ref "R23") (pin "1") (pinfunction "1_1") (pintype "passive"))
    )
    (net (code "26") (name "Net-(L1-Pad2)") (class "Default")
      (node (ref "L1") (pin "2") (pinfunction "2_2") (pintype "passive"))
      (node (ref "L2") (pin "1") (pinfunction "1_1") (pintype "passive"))
    )
    (net (code "27") (name "Net-(L2-Pad2)") (class "Default")
      (node (ref "L2") (pin "2") (pinfunction "2_2") (pintype "passive"))
      (node (ref "L3") (pin "1") (pinfunction "1_1") (pintype "passive"))
    )
    (net (code "28") (name "Net-(L3-Pad2)") (class "Default")
      (node (ref "L3") (pin "2") (pinfunction "2_2") (pintype "passive"))
      (node (ref "L4") (pin "1") (pinfunction "1_1") (pintype "passive"))
    )
    (net (code "29") (name "Net-(L4-Pad2)") (class "Default")
      (node (ref "L4") (pin "2") (pinfunction "2_2") (pintype "passive"))
      (node (ref "L5") (pin "1") (pinfunction "1_1") (pintype "passive"))
    )
    (net (code "30") (name "Net-(Q2-G)") (class "Default")
      (node (ref "D15") (pin "A") (pinfunction "A_A") (pintype "passive"))
      (node (ref "Q2") (pin "1") (pinfunction "G_1") (pintype "passive"))
      (node (ref "R7") (pin "2") (pinfunction "2_2") (pintype "passive"))
    )
    (net (code "31") (name "Net-(Q3-G)") (class "Default")
      (node (ref "D14") (pin "A") (pinfunction "A_A") (pintype "passive"))
      (node (ref "Q3") (pin "1") (pinfunction "G_1") (pintype "passive"))
      (node (ref "R6") (pin "2") (pinfunction "2_2") (pintype "passive"))
    )
    (net (code "32") (name "Net-(Q4-G)") (class "Default")
      (node (ref "D18") (pin "A") (pinfunction "A_A") (pintype "passive"))
      (node (ref "Q4") (pin "1") (pinfunction "G_1") (pintype "passive"))
      (node (ref "R13") (pin "2") (pinfunction "2_2") (pintype "passive"))
    )
    (net (code "33") (name "Net-(Q5-G)") (class "Default")
      (node (ref "D17") (pin "A") (pinfunction "A_A") (pintype "passive"))
      (node (ref "Q5") (pin "1") (pinfunction "G_1") (pintype "passive"))
      (node (ref "R12") (pin "2") (pinfunction "2_2") (pintype "passive"))
    )
    (net (code "34") (name "Net-(Q6-G)") (class "Default")
      (node (ref "D24") (pin "A") (pinfunction "A_A") (pintype "passive"))
      (node (ref "Q6") (pin "1") (pinfunction "G_1") (pintype "passive"))
      (node (ref "R21") (pin "2") (pinfunction "2_2") (pintype "passive"))
    )
    (net (code "35") (name "Net-(Q7-G)") (class "Default")
      (node (ref "D25") (pin "A") (pinfunction "A_A") (pintype "passive"))
      (node (ref "Q7") (pin "1") (pinfunction "G_1") (pintype "passive"))
      (node (ref "R24") (pin "2") (pinfunction "2_2") (pintype "passive"))
    )
    (net (code "36") (name "Net-(U5-FILTER)") (class "Default")
      (node (ref "C19") (pin "2") (pinfunction "2_2") (pintype "passive"))
      (node (ref "U5") (pin "6") (pinfunction "FILTER_6") (pintype "input"))
    )
    (net (code "37") (name "Net-(U5-VIOUT)") (class "Default")
      (node (ref "R18") (pin "2") (pinfunction "2_2") (pintype "passive"))
      (node (ref "U5") (pin "7") (pinfunction "VIOUT_7") (pintype "output"))
    )
    (net (code "38") (name "Net-(U6-FILTER)") (class "Default")
      (node (ref "C22") (pin "2") (pinfunction "2_2") (pintype "passive"))
      (node (ref "U6") (pin "6") (pinfunction "FILTER_6") (pintype "input"))
    )
    (net (code "39") (name "Net-(U6-VIOUT)") (class "Default")
      (node (ref "R28") (pin "2") (pinfunction "2_2") (pintype "passive"))
      (node (ref "U6") (pin "7") (pinfunction "VIOUT_7") (pintype "output"))
    )
  )
)
